# adc.net
KiCad netlist of a schematic drawn in Altium Designer
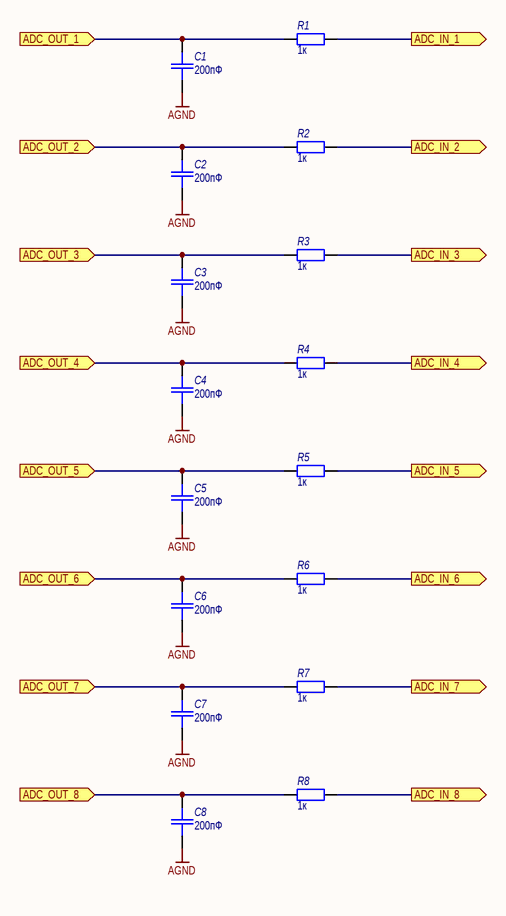
[diagram p0: adc.SchDoc]

(export (version "E")
  (design (tool "Eeschema 10.0.6"))
  (components
    (comp (ref "C1")
      (value "200пФ")
      (footprint "SMD_0805")
      (description "Capacitor")
      (libsource (lib "Passive") (part "Capacitor"))
    )
    (comp (ref "C2")
      (value "200пФ")
      (footprint "SMD_0805")
      (description "Capacitor")
      (libsource (lib "Passive") (part "Capacitor"))
    )
    (comp (ref "C3")
      (value "200пФ")
      (footprint "SMD_0805")
      (description "Capacitor")
      (libsource (lib "Passive") (part "Capacitor"))
    )
    (comp (ref "C4")
      (value "200пФ")
      (footprint "SMD_0805")
      (description "Capacitor")
      (libsource (lib "Passive") (part "Capacitor"))
    )
    (comp (ref "C5")
      (value "200пФ")
      (footprint "SMD_0805")
      (description "Capacitor")
      (libsource (lib "Passive") (part "Capacitor"))
    )
    (comp (ref "C6")
      (value "200пФ")
      (footprint "SMD_0805")
      (description "Capacitor")
      (libsource (lib "Passive") (part "Capacitor"))
    )
    (comp (ref "C7")
      (value "200пФ")
      (footprint "SMD_0805")
      (description "Capacitor")
      (libsource (lib "Passive") (part "Capacitor"))
    )
    (comp (ref "C8")
      (value "200пФ")
      (footprint "SMD_0805")
      (description "Capacitor")
      (libsource (lib "Passive") (part "Capacitor"))
    )
    (comp (ref "R1")
      (value "1к")
      (footprint "SMD_0805")
      (description "Resistor")
      (libsource (lib "Passive") (part "Resistor"))
    )
    (comp (ref "R2")
      (value "1к")
      (footprint "SMD_0805")
      (description "Resistor")
      (libsource (lib "Passive") (part "Resistor"))
    )
    (comp (ref "R3")
      (value "1к")
      (footprint "SMD_0805")
      (description "Resistor")
      (libsource (lib "Passive") (part "Resistor"))
    )
    (comp (ref "R4")
      (value "1к")
      (footprint "SMD_0805")
      (description "Resistor")
      (libsource (lib "Passive") (part "Resistor"))
    )
    (comp (ref "R5")
      (value "1к")
      (footprint "SMD_0805")
      (description "Resistor")
      (libsource (lib "Passive") (part "Resistor"))
    )
    (comp (ref "R6")
      (value "1к")
      (footprint "SMD_0805")
      (description "Resistor")
      (libsource (lib "Passive") (part "Resistor"))
    )
    (comp (ref "R7")
      (value "1к")
      (footprint "SMD_0805")
      (description "Resistor")
      (libsource (lib "Passive") (part "Resistor"))
    )
    (comp (ref "R8")
      (value "1к")
      (footprint "SMD_0805")
      (description "Resistor")
      (libsource (lib "Passive") (part "Resistor"))
    )
  )
  (nets
    (net (code "1") (name "/ADC_IN_1") (class "Default")
      (node (ref "R1") (pin "2") (pinfunction "2_2") (pintype "passive"))
    )
    (net (code "2") (name "/ADC_IN_2") (class "Default")
      (node (ref "R2") (pin "2") (pinfunction "2_2") (pintype "passive"))
    )
    (net (code "3") (name "/ADC_IN_3") (class "Default")
      (node (ref "R3") (pin "2") (pinfunction "2_2") (pintype "passive"))
    )
    (net (code "4") (name "/ADC_IN_4") (class "Default")
      (node (ref "R4") (pin "2") (pinfunction "2_2") (pintype "passive"))
    )
    (net (code "5") (name "/ADC_IN_5") (class "Default")
      (node (ref "R5") (pin "2") (pinfunction "2_2") (pintype "passive"))
    )
    (net (code "6") (name "/ADC_IN_6") (class "Default")
      (node (ref "R6") (pin "2") (pinfunction "2_2") (pintype "passive"))
    )
    (net (code "7") (name "/ADC_IN_7") (class "Default")
      (node (ref "R7") (pin "2") (pinfunction "2_2") (pintype "passive"))
    )
    (net (code "8") (name "/ADC_IN_8") (class "Default")
      (node (ref "R8") (pin "2") (pinfunction "2_2") (pintype "passive"))
    )
    (net (code "9") (name "/ADC_OUT_1") (class "Default")
      (node (ref "C1") (pin "2") (pinfunction "2_2") (pintype "passive"))
      (node (ref "R1") (pin "1") (pinfunction "1_1") (pintype "passive"))
    )
    (net (code "10") (name "/ADC_OUT_2") (class "Default")
      (node (ref "C2") (pin "2") (pinfunction "2_2") (pintype "passive"))
      (node (ref "R2") (pin "1") (pinfunction "1_1") (pintype "passive"))
    )
    (net (code "11") (name "/ADC_OUT_3") (class "Default")
      (node (ref "C3") (pin "2") (pinfunction "2_2") (pintype "passive"))
      (node (ref "R3") (pin "1") (pinfunction "1_1") (pintype "passive"))
    )
    (net (code "12") (name "/ADC_OUT_4") (class "Default")
      (node (ref "C4") (pin "2") (pinfunction "2_2") (pintype "passive"))
      (node (ref "R4") (pin "1") (pinfunction "1_1") (pintype "passive"))
    )
    (net (code "13") (name "/ADC_OUT_5") (class "Default")
      (node (ref "C5") (pin "2") (pinfunction "2_2") (pintype "passive"))
      (node (ref "R5") (pin "1") (pinfunction "1_1") (pintype "passive"))
    )
    (net (code "14") (name "/ADC_OUT_6") (class "Default")
      (node (ref "C6") (pin "2") (pinfunction "2_2") (pintype "passive"))
      (node (ref "R6") (pin "1") (pinfunction "1_1") (pintype "passive"))
    )
    (net (code "15") (name "/ADC_OUT_7") (class "Default")
      (node (ref "C7") (pin "2") (pinfunction "2_2") (pintype "passive"))
      (node (ref "R7") (pin "1") (pinfunction "1_1") (pintype "passive"))
    )
    (net (code "16") (name "/ADC_OUT_8") (class "Default")
      (node (ref "C8") (pin "2") (pinfunction "2_2") (pintype "passive"))
      (node (ref "R8") (pin "1") (pinfunction "1_1") (pintype "passive"))
    )
    (net (code "17") (name "AGND") (class "Default")
      (node (ref "C1") (pin "1") (pinfunction "1_1") (pintype "passive"))
      (node (ref "C2") (pin "1") (pinfunction "1_1") (pintype "passive"))
      (node (ref "C3") (pin "1") (pinfunction "1_1") (pintype "passive"))
      (node (ref "C4") (pin "1") (pinfunction "1_1") (pintype "passive"))
      (node (ref "C5") (pin "1") (pinfunction "1_1") (pintype "passive"))
      (node (ref "C6") (pin "1") (pinfunction "1_1") (pintype "passive"))
      (node (ref "C7") (pin "1") (pinfunction "1_1") (pintype "passive"))
      (node (ref "C8") (pin "1") (pinfunction "1_1") (pintype "passive"))
    )
  )
)
